# cpu.net
KiCad netlist of a schematic drawn in Altium Designer
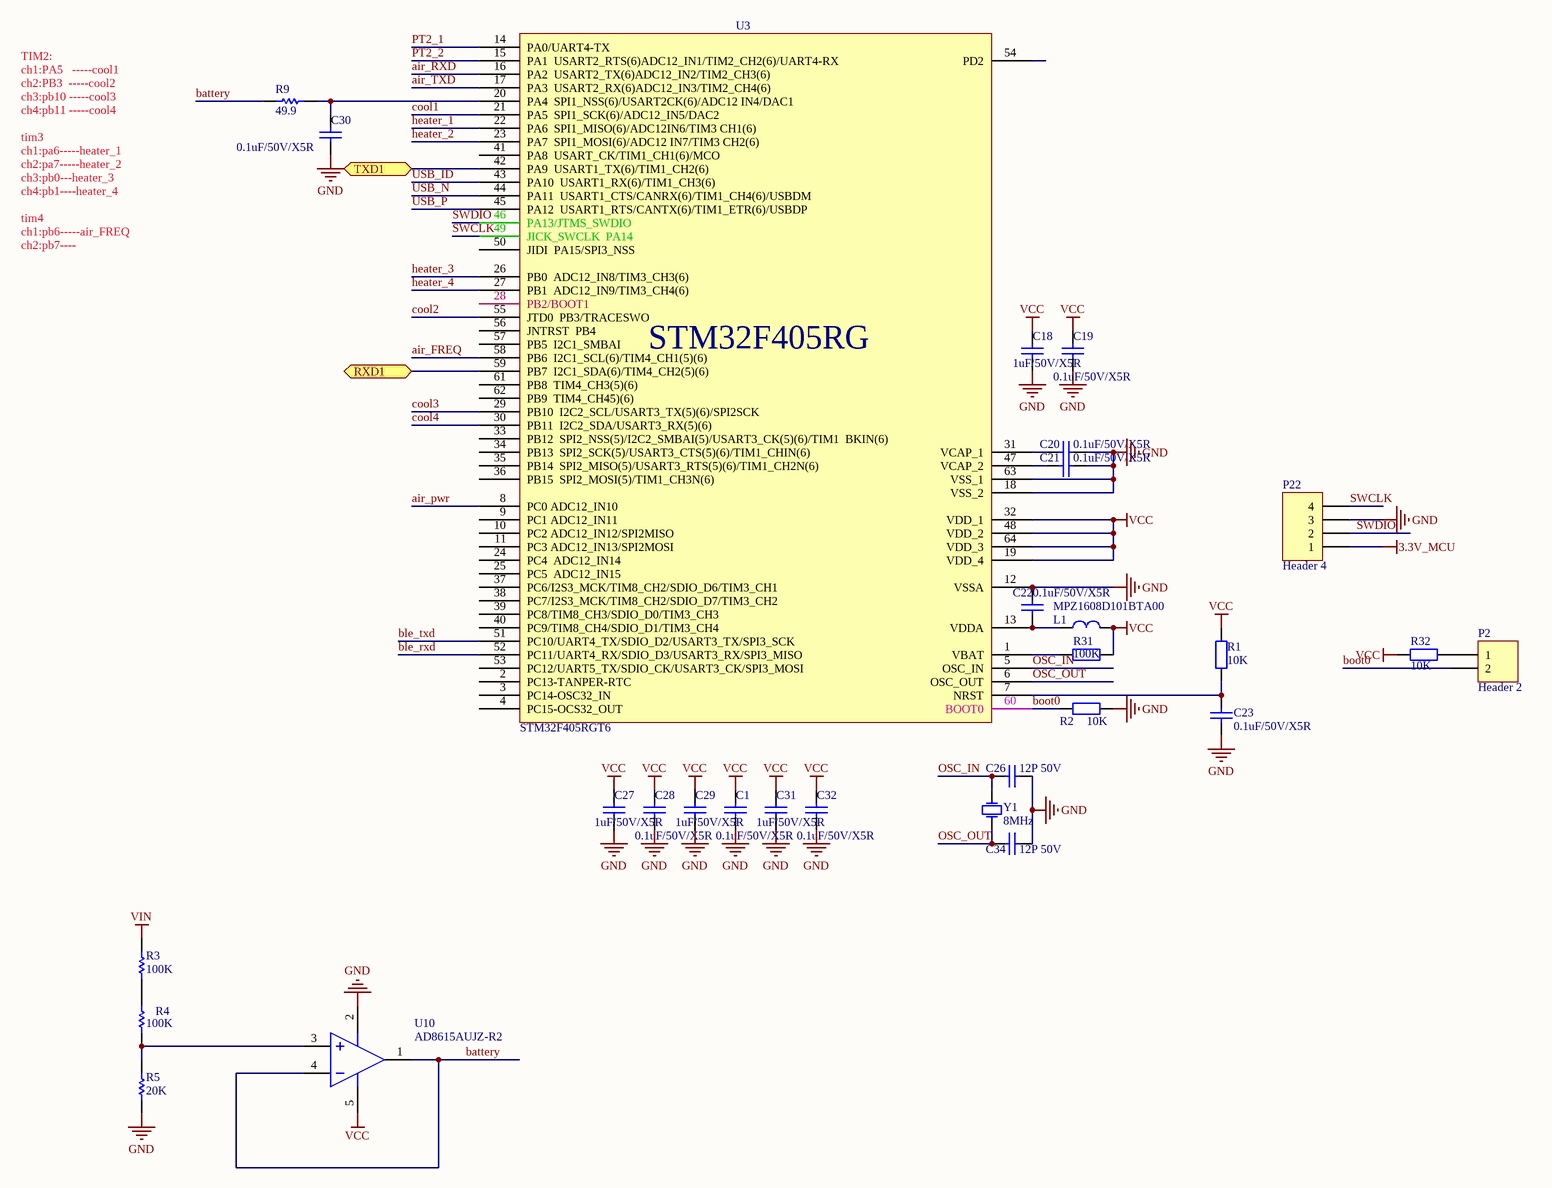
[diagram p0: cpu.SchDoc]

(export (version "E")
  (design (tool "Eeschema 10.0.6"))
  (components
    (comp (ref "C1")
      (value "0.1uF/50V/X5R")
      (footprint "0603C")
      (description "贴片电容 20%")
      (libsource (lib "XiaoyI") (part "CAP4"))
    )
    (comp (ref "C18")
      (value "1uF/50V/X5R")
      (footprint "0603C")
      (description "贴片电容 20%")
      (libsource (lib "XiaoyI") (part "CAP4"))
    )
    (comp (ref "C19")
      (value "0.1uF/50V/X5R")
      (footprint "0603C")
      (description "贴片电容 20%")
      (libsource (lib "XiaoyI") (part "CAP4"))
    )
    (comp (ref "C20")
      (value "0.1uF/50V/X5R")
      (footprint "0603C")
      (description "贴片电容 20%")
      (libsource (lib "XiaoyI") (part "CAP4"))
    )
    (comp (ref "C21")
      (value "0.1uF/50V/X5R")
      (footprint "0603C")
      (description "贴片电容 20%")
      (libsource (lib "XiaoyI") (part "CAP4"))
    )
    (comp (ref "C22")
      (value "0.1uF/50V/X5R")
      (footprint "0603C")
      (description "贴片电容 20%")
      (libsource (lib "XiaoyI") (part "CAP4"))
    )
    (comp (ref "C23")
      (value "0.1uF/50V/X5R")
      (footprint "0603C")
      (description "贴片电容 20%")
      (libsource (lib "XiaoyI") (part "CAP4"))
    )
    (comp (ref "C26")
      (value "12P 50V")
      (footprint "0603C")
      (description "贴片电容 20%")
      (libsource (lib "XiaoyI") (part "CAP4"))
    )
    (comp (ref "C27")
      (value "1uF/50V/X5R")
      (footprint "0603C")
      (description "贴片电容 20%")
      (libsource (lib "XiaoyI") (part "CAP4"))
    )
    (comp (ref "C28")
      (value "0.1uF/50V/X5R")
      (footprint "0603C")
      (description "贴片电容 20%")
      (libsource (lib "XiaoyI") (part "CAP4"))
    )
    (comp (ref "C29")
      (value "1uF/50V/X5R")
      (footprint "0603C")
      (description "贴片电容 20%")
      (libsource (lib "XiaoyI") (part "CAP4"))
    )
    (comp (ref "C30")
      (value "0.1uF/50V/X5R")
      (footprint "0603C")
      (description "贴片电容 20%")
      (libsource (lib "XiaoyI") (part "CAP4"))
    )
    (comp (ref "C31")
      (value "1uF/50V/X5R")
      (footprint "0603C")
      (description "贴片电容 20%")
      (libsource (lib "XiaoyI") (part "CAP4"))
    )
    (comp (ref "C32")
      (value "0.1uF/50V/X5R")
      (footprint "0603C")
      (description "贴片电容 20%")
      (libsource (lib "XiaoyI") (part "CAP4"))
    )
    (comp (ref "C34")
      (value "12P 50V")
      (footprint "0603C")
      (description "贴片电容 20%")
      (libsource (lib "XiaoyI") (part "CAP4"))
    )
    (comp (ref "L1")
      (value "MPZ1608D101BTA00")
      (footprint "0603R")
      (description "磁珠电感 100R 100MHz")
      (libsource (lib "XiaoyI") (part "CIZHU1"))
    )
    (comp (ref "P2")
      (value "Header 2")
      (footprint "HDR1X2")
      (description "Header, 2-Pin")
      (fields (field (name "PUBLISHER") "Altium Limited"))
      (libsource (lib "Miscellaneous Connectors") (part "Header 2"))
    )
    (comp (ref "P22")
      (value "Header 4")
      (footprint "HDR1X4")
      (description "Header, 4-Pin")
      (fields (field (name "PUBLISHER") "Altium Limited"))
      (libsource (lib "Miscellaneous Connectors") (part "Header 4"))
    )
    (comp (ref "R1")
      (value "10K")
      (footprint "0603R")
      (description "贴片电阻 5%")
      (libsource (lib "") (part "RES2_1"))
    )
    (comp (ref "R2")
      (value "10K")
      (footprint "0603R")
      (description "贴片电阻 5%")
      (libsource (lib "XiaoyI") (part "RES2"))
    )
    (comp (ref "R3")
      (value "100K")
      (footprint "0603R")
      (description "Resistor")
      (fields (field (name "PUBLISHER") "Altium Limited"))
      (libsource (lib "Miscellaneous Devices") (part "Res1"))
    )
    (comp (ref "R4")
      (value "100K")
      (footprint "0603R")
      (description "Resistor")
      (fields (field (name "PUBLISHER") "Altium Limited"))
      (libsource (lib "Miscellaneous Devices") (part "Res1"))
    )
    (comp (ref "R5")
      (value "20K")
      (footprint "0603R")
      (description "Resistor")
      (fields (field (name "PUBLISHER") "Altium Limited"))
      (libsource (lib "Miscellaneous Devices") (part "Res1"))
    )
    (comp (ref "R9")
      (value "49.9")
      (footprint "0603R")
      (description "Resistor")
      (fields (field (name "PUBLISHER") "Altium Limited"))
      (libsource (lib "Miscellaneous Devices") (part "Res1"))
    )
    (comp (ref "R31")
      (value "100K")
      (footprint "0603R")
      (description "贴片电阻 5%")
      (libsource (lib "") (part "RES2_2"))
    )
    (comp (ref "R32")
      (value "10K")
      (footprint "0603R")
      (description "贴片电阻 5%")
      (libsource (lib "") (part "RES2_2"))
    )
    (comp (ref "U3")
      (value "STM32F405RGT6")
      (footprint "LQFP-64")
      (description "MCU")
      (libsource (lib "XiaoyI") (part "STM32F405RG"))
    )
    (comp (ref "U10")
      (value "AD8615AUJZ-R2")
      (footprint "sot-23-5")
      (libsource (lib "Schlib1") (part "AD8615"))
    )
    (comp (ref "Y1")
      (value "8MHz")
      (footprint "CRAY_5032")
      (description "晶振")
      (libsource (lib "XiaoyI") (part "XTAL"))
    )
  )
  (nets
    (net (code "1") (name "/OSC_IN") (class "Default")
      (node (ref "C26") (pin "2") (pinfunction "2_2") (pintype "passive"))
      (node (ref "U3") (pin "5") (pinfunction "OSC_IN_5") (pintype "passive"))
      (node (ref "Y1") (pin "2") (pinfunction "OSC2_2") (pintype "passive"))
    )
    (net (code "2") (name "/OSC_OUT") (class "Default")
      (node (ref "C34") (pin "2") (pinfunction "2_2") (pintype "passive"))
      (node (ref "U3") (pin "6") (pinfunction "OSC_OUT_6") (pintype "passive"))
      (node (ref "Y1") (pin "1") (pinfunction "OSC1_1") (pintype "passive"))
    )
    (net (code "3") (name "/PT2_1") (class "Default")
      (node (ref "U3") (pin "14") (pinfunction "PA0/UART4-TX_14") (pintype "passive"))
    )
    (net (code "4") (name "/PT2_2") (class "Default")
      (node (ref "U3") (pin "15") (pinfunction "PA1__USART2_RTS(6)ADC12_IN1/TIM2_CH2(6)/UART4-RX_15") (pintype "passive"))
    )
    (net (code "5") (name "/RXD1") (class "Default")
      (node (ref "U3") (pin "59") (pinfunction "PB7__I2C1_SDA(6)/TIM4_CH2(5)(6)_59") (pintype "passive"))
    )
    (net (code "6") (name "/SWCLK") (class "Default")
      (node (ref "P22") (pin "4") (pinfunction "4_4") (pintype "passive"))
      (node (ref "U3") (pin "49") (pinfunction "JICK_SWCLK__PA14_49") (pintype "passive"))
    )
    (net (code "7") (name "/SWDIO") (class "Default")
      (node (ref "P22") (pin "2") (pinfunction "2_2") (pintype "passive"))
      (node (ref "U3") (pin "46") (pinfunction "PA13/JTMS_SWDIO_46") (pintype "passive"))
    )
    (net (code "8") (name "/TXD1") (class "Default")
      (node (ref "U3") (pin "42") (pinfunction "PA9__USART1_TX(6)/TIM1_CH2(6)_42") (pintype "passive"))
    )
    (net (code "9") (name "/USB_ID") (class "Default")
      (node (ref "U3") (pin "43") (pinfunction "PA10__USART1_RX(6)/TIM1_CH3(6)_43") (pintype "passive"))
    )
    (net (code "10") (name "/USB_N") (class "Default")
      (node (ref "U3") (pin "44") (pinfunction "PA11__USART1_CTS/CANRX(6)/TIM1_CH4(6)/USBDM_44") (pintype "passive"))
    )
    (net (code "11") (name "/USB_P") (class "Default")
      (node (ref "U3") (pin "45") (pinfunction "PA12__USART1_RTS/CANTX(6)/TIM1_ETR(6)/USBDP_45") (pintype "passive"))
    )
    (net (code "12") (name "/air_FREQ") (class "Default")
      (node (ref "U3") (pin "58") (pinfunction "PB6__I2C1_SCL(6)/TIM4_CH1(5)(6)_58") (pintype "passive"))
    )
    (net (code "13") (name "/air_RXD") (class "Default")
      (node (ref "U3") (pin "16") (pinfunction "PA2__USART2_TX(6)ADC12_IN2/TIM2_CH3(6)_16") (pintype "passive"))
    )
    (net (code "14") (name "/air_TXD") (class "Default")
      (node (ref "U3") (pin "17") (pinfunction "PA3__USART2_RX(6)ADC12_IN3/TIM2_CH4(6)_17") (pintype "passive"))
    )
    (net (code "15") (name "/air_pwr") (class "Default")
      (node (ref "U3") (pin "8") (pinfunction "PC0_ADC12_IN10_8") (pintype "passive"))
    )
    (net (code "16") (name "/battery") (class "Default")
      (node (ref "R9") (pin "1") (pinfunction "1_1") (pintype "passive"))
      (node (ref "U10") (pin "1") (pinfunction "OS_NUL_1") (pintype "passive"))
      (node (ref "U10") (pin "4") (pinfunction "V-_4") (pintype "power_in"))
    )
    (net (code "17") (name "/ble_rxd") (class "Default")
      (node (ref "U3") (pin "52") (pinfunction "PC11/UART4_RX/SDIO_D3/USART3_RX/SPI3_MISO_52") (pintype "passive"))
    )
    (net (code "18") (name "/ble_txd") (class "Default")
      (node (ref "U3") (pin "51") (pinfunction "PC10/UART4_TX/SDIO_D2/USART3_TX/SPI3_SCK_51") (pintype "passive"))
    )
    (net (code "19") (name "/boot0") (class "Default")
      (node (ref "P2") (pin "2") (pinfunction "2_2") (pintype "passive"))
      (node (ref "R2") (pin "1") (pinfunction "1_1") (pintype "passive"))
      (node (ref "U3") (pin "60") (pinfunction "BOOT0_60") (pintype "passive"))
    )
    (net (code "20") (name "/cool1") (class "Default")
      (node (ref "U3") (pin "21") (pinfunction "PA5__SPI1_SCK(6)/ADC12_IN5/DAC2_21") (pintype "passive"))
    )
    (net (code "21") (name "/cool2") (class "Default")
      (node (ref "U3") (pin "55") (pinfunction "JTD0__PB3/TRACESWO_55") (pintype "passive"))
    )
    (net (code "22") (name "/cool3") (class "Default")
      (node (ref "U3") (pin "29") (pinfunction "PB10__I2C2_SCL/USART3_TX(5)(6)/SPI2SCK_29") (pintype "passive"))
    )
    (net (code "23") (name "/cool4") (class "Default")
      (node (ref "U3") (pin "30") (pinfunction "PB11__I2C2_SDA/USART3_RX(5)(6)_30") (pintype "passive"))
    )
    (net (code "24") (name "/heater_1") (class "Default")
      (node (ref "U3") (pin "22") (pinfunction "PA6__SPI1_MISO(6)/ADC12IN6/TIM3_CH1(6)_22") (pintype "passive"))
    )
    (net (code "25") (name "/heater_2") (class "Default")
      (node (ref "U3") (pin "23") (pinfunction "PA7__SPI1_MOSI(6)/ADC12_IN7/TIM3_CH2(6)_23") (pintype "passive"))
    )
    (net (code "26") (name "/heater_3") (class "Default")
      (node (ref "U3") (pin "26") (pinfunction "PB0__ADC12_IN8/TIM3_CH3(6)_26") (pintype "passive"))
    )
    (net (code "27") (name "/heater_4") (class "Default")
      (node (ref "U3") (pin "27") (pinfunction "PB1__ADC12_IN9/TIM3_CH4(6)_27") (pintype "passive"))
    )
    (net (code "28") (name "3.3V_MCU") (class "Default")
      (node (ref "P22") (pin "1") (pinfunction "1_1") (pintype "passive"))
    )
    (net (code "29") (name "GND") (class "Default")
      (node (ref "C1") (pin "1") (pinfunction "1_1") (pintype "passive"))
      (node (ref "C18") (pin "1") (pinfunction "1_1") (pintype "passive"))
      (node (ref "C19") (pin "1") (pinfunction "1_1") (pintype "passive"))
      (node (ref "C20") (pin "1") (pinfunction "1_1") (pintype "passive"))
      (node (ref "C21") (pin "1") (pinfunction "1_1") (pintype "passive"))
      (node (ref "C22") (pin "1") (pinfunction "1_1") (pintype "passive"))
      (node (ref "C23") (pin "1") (pinfunction "1_1") (pintype "passive"))
      (node (ref "C26") (pin "1") (pinfunction "1_1") (pintype "passive"))
      (node (ref "C27") (pin "1") (pinfunction "1_1") (pintype "passive"))
      (node (ref "C28") (pin "1") (pinfunction "1_1") (pintype "passive"))
      (node (ref "C29") (pin "1") (pinfunction "1_1") (pintype "passive"))
      (node (ref "C30") (pin "1") (pinfunction "1_1") (pintype "passive"))
      (node (ref "C31") (pin "1") (pinfunction "1_1") (pintype "passive"))
      (node (ref "C32") (pin "1") (pinfunction "1_1") (pintype "passive"))
      (node (ref "C34") (pin "1") (pinfunction "1_1") (pintype "passive"))
      (node (ref "P22") (pin "3") (pinfunction "3_3") (pintype "passive"))
      (node (ref "R2") (pin "2") (pinfunction "2_2") (pintype "passive"))
      (node (ref "R5") (pin "2") (pinfunction "2_2") (pintype "passive"))
      (node (ref "U10") (pin "2") (pinfunction "G_2") (pintype "power_in"))
      (node (ref "U3") (pin "12") (pinfunction "VSSA_12") (pintype "passive"))
      (node (ref "U3") (pin "18") (pinfunction "VSS_2_18") (pintype "passive"))
      (node (ref "U3") (pin "63") (pinfunction "VSS_1_63") (pintype "passive"))
    )
    (net (code "30") (name "Net-(P2-Pad1)") (class "Default")
      (node (ref "P2") (pin "1") (pinfunction "1_1") (pintype "passive"))
      (node (ref "R32") (pin "1") (pinfunction "1_1") (pintype "passive"))
    )
    (net (code "31") (name "Net-(R3-Pad2)") (class "Default")
      (node (ref "R3") (pin "2") (pinfunction "2_2") (pintype "passive"))
      (node (ref "R4") (pin "1") (pinfunction "1_1") (pintype "passive"))
    )
    (net (code "32") (name "Net-(U3-NRST)") (class "Default")
      (node (ref "C23") (pin "2") (pinfunction "2_2") (pintype "passive"))
      (node (ref "R1") (pin "2") (pinfunction "2_2") (pintype "passive"))
      (node (ref "U3") (pin "7") (pinfunction "NRST_7") (pintype "passive"))
    )
    (net (code "33") (name "Net-(U3-PA4__SPI1_NSS(6){slash}USART2CK(6){slash}ADC12_IN4{slash}DAC1)") (class "Default")
      (node (ref "C30") (pin "2") (pinfunction "2_2") (pintype "passive"))
      (node (ref "R9") (pin "2") (pinfunction "2_2") (pintype "passive"))
      (node (ref "U3") (pin "20") (pinfunction "PA4__SPI1_NSS(6)/USART2CK(6)/ADC12_IN4/DAC1_20") (pintype "passive"))
    )
    (net (code "34") (name "Net-(U3-VBAT)") (class "Default")
      (node (ref "R31") (pin "2") (pinfunction "2_2") (pintype "passive"))
      (node (ref "U3") (pin "1") (pinfunction "VBAT_1") (pintype "passive"))
    )
    (net (code "35") (name "Net-(U3-VCAP_1)") (class "Default")
      (node (ref "C20") (pin "2") (pinfunction "2_2") (pintype "passive"))
      (node (ref "U3") (pin "31") (pinfunction "VCAP_1_31") (pintype "passive"))
    )
    (net (code "36") (name "Net-(U3-VCAP_2)") (class "Default")
      (node (ref "C21") (pin "2") (pinfunction "2_2") (pintype "passive"))
      (node (ref "U3") (pin "47") (pinfunction "VCAP_2_47") (pintype "passive"))
    )
    (net (code "37") (name "Net-(U3-VDDA)") (class "Default")
      (node (ref "C22") (pin "2") (pinfunction "2_2") (pintype "passive"))
      (node (ref "L1") (pin "1") (pinfunction "1_1") (pintype "passive"))
      (node (ref "U3") (pin "13") (pinfunction "VDDA_13") (pintype "passive"))
    )
    (net (code "38") (name "Net-(U10-V+)") (class "Default")
      (node (ref "R4") (pin "2") (pinfunction "2_2") (pintype "passive"))
      (node (ref "R5") (pin "1") (pinfunction "1_1") (pintype "passive"))
      (node (ref "U10") (pin "3") (pinfunction "V+_3") (pintype "power_in"))
    )
    (net (code "39") (name "VCC") (class "Default")
      (node (ref "C1") (pin "2") (pinfunction "2_2") (pintype "passive"))
      (node (ref "C18") (pin "2") (pinfunction "2_2") (pintype "passive"))
      (node (ref "C19") (pin "2") (pinfunction "2_2") (pintype "passive"))
      (node (ref "C27") (pin "2") (pinfunction "2_2") (pintype "passive"))
      (node (ref "C28") (pin "2") (pinfunction "2_2") (pintype "passive"))
      (node (ref "C29") (pin "2") (pinfunction "2_2") (pintype "passive"))
      (node (ref "C31") (pin "2") (pinfunction "2_2") (pintype "passive"))
      (node (ref "C32") (pin "2") (pinfunction "2_2") (pintype "passive"))
      (node (ref "L1") (pin "2") (pinfunction "2_2") (pintype "passive"))
      (node (ref "R1") (pin "1") (pinfunction "1_1") (pintype "passive"))
      (node (ref "R31") (pin "1") (pinfunction "1_1") (pintype "passive"))
      (node (ref "R32") (pin "2") (pinfunction "2_2") (pintype "passive"))
      (node (ref "U10") (pin "5") (pinfunction "VCC_5") (pintype "passive"))
      (node (ref "U3") (pin "19") (pinfunction "VDD_4_19") (pintype "passive"))
      (node (ref "U3") (pin "32") (pinfunction "VDD_1_32") (pintype "passive"))
      (node (ref "U3") (pin "48") (pinfunction "VDD_2_48") (pintype "passive"))
      (node (ref "U3") (pin "64") (pinfunction "VDD_3_64") (pintype "passive"))
    )
    (net (code "40") (name "VIN") (class "Default")
      (node (ref "R3") (pin "1") (pinfunction "1_1") (pintype "passive"))
    )
    (net (code "41") (name "unconnected-(U3-JIDI__PA15{slash}SPI3_NSS-Pad50)") (class "Default")
      (node (ref "U3") (pin "50") (pinfunction "JIDI__PA15/SPI3_NSS_50") (pintype "passive"))
    )
    (net (code "42") (name "unconnected-(U3-JNTRST__PB4-Pad56)") (class "Default")
      (node (ref "U3") (pin "56") (pinfunction "JNTRST__PB4_56") (pintype "passive"))
    )
    (net (code "43") (name "unconnected-(U3-PA8__USART_CK{slash}TIM1_CH1(6){slash}MCO-Pad41)") (class "Default")
      (node (ref "U3") (pin "41") (pinfunction "PA8__USART_CK/TIM1_CH1(6)/MCO_41") (pintype "passive"))
    )
    (net (code "44") (name "unconnected-(U3-PB2{slash}BOOT1-Pad28)") (class "Default")
      (node (ref "U3") (pin "28") (pinfunction "PB2/BOOT1_28") (pintype "passive"))
    )
    (net (code "45") (name "unconnected-(U3-PB5__I2C1_SMBAI-Pad57)") (class "Default")
      (node (ref "U3") (pin "57") (pinfunction "PB5__I2C1_SMBAI_57") (pintype "passive"))
    )
    (net (code "46") (name "unconnected-(U3-PB8__TIM4_CH3(5)(6)-Pad61)") (class "Default")
      (node (ref "U3") (pin "61") (pinfunction "PB8__TIM4_CH3(5)(6)_61") (pintype "passive"))
    )
    (net (code "47") (name "unconnected-(U3-PB9__TIM4_CH45)(6)-Pad62)") (class "Default")
      (node (ref "U3") (pin "62") (pinfunction "PB9__TIM4_CH45)(6)_62") (pintype "passive"))
    )
    (net (code "48") (name "unconnected-(U3-PB12__SPI2_NSS(5){slash}I2C2_SMBAI(5){slash}USART3_CK(5)(6){slash}TIM1__BKIN(6)-Pad33)") (class "Default")
      (node (ref "U3") (pin "33") (pinfunction "PB12__SPI2_NSS(5)/I2C2_SMBAI(5)/USART3_CK(5)(6)/TIM1__BKIN(6)_33") (pintype "passive"))
    )
    (net (code "49") (name "unconnected-(U3-PB13__SPI2_SCK(5){slash}USART3_CTS(5)(6){slash}TIM1_CHIN(6)-Pad34)") (class "Default")
      (node (ref "U3") (pin "34") (pinfunction "PB13__SPI2_SCK(5)/USART3_CTS(5)(6)/TIM1_CHIN(6)_34") (pintype "passive"))
    )
    (net (code "50") (name "unconnected-(U3-PB14__SPI2_MISO(5){slash}USART3_RTS(5)(6){slash}TIM1_CH2N(6)-Pad35)") (class "Default")
      (node (ref "U3") (pin "35") (pinfunction "PB14__SPI2_MISO(5)/USART3_RTS(5)(6)/TIM1_CH2N(6)_35") (pintype "passive"))
    )
    (net (code "51") (name "unconnected-(U3-PB15__SPI2_MOSI(5){slash}TIM1_CH3N(6)-Pad36)") (class "Default")
      (node (ref "U3") (pin "36") (pinfunction "PB15__SPI2_MOSI(5)/TIM1_CH3N(6)_36") (pintype "passive"))
    )
    (net (code "52") (name "unconnected-(U3-PC1_ADC12_IN11-Pad9)") (class "Default")
      (node (ref "U3") (pin "9") (pinfunction "PC1_ADC12_IN11_9") (pintype "passive"))
    )
    (net (code "53") (name "unconnected-(U3-PC2_ADC12_IN12{slash}SPI2MISO-Pad10)") (class "Default")
      (node (ref "U3") (pin "10") (pinfunction "PC2_ADC12_IN12/SPI2MISO_10") (pintype "passive"))
    )
    (net (code "54") (name "unconnected-(U3-PC3_ADC12_IN13{slash}SPI2MOSI-Pad11)") (class "Default")
      (node (ref "U3") (pin "11") (pinfunction "PC3_ADC12_IN13/SPI2MOSI_11") (pintype "passive"))
    )
    (net (code "55") (name "unconnected-(U3-PC4__ADC12_IN14-Pad24)") (class "Default")
      (node (ref "U3") (pin "24") (pinfunction "PC4__ADC12_IN14_24") (pintype "passive"))
    )
    (net (code "56") (name "unconnected-(U3-PC5__ADC12_IN15-Pad25)") (class "Default")
      (node (ref "U3") (pin "25") (pinfunction "PC5__ADC12_IN15_25") (pintype "passive"))
    )
    (net (code "57") (name "unconnected-(U3-PC6{slash}I2S3_MCK{slash}TIM8_CH2{slash}SDIO_D6{slash}TIM3_CH1-Pad37)") (class "Default")
      (node (ref "U3") (pin "37") (pinfunction "PC6/I2S3_MCK/TIM8_CH2/SDIO_D6/TIM3_CH1_37") (pintype "passive"))
    )
    (net (code "58") (name "unconnected-(U3-PC7{slash}I2S3_MCK{slash}TIM8_CH2{slash}SDIO_D7{slash}TIM3_CH2-Pad38)") (class "Default")
      (node (ref "U3") (pin "38") (pinfunction "PC7/I2S3_MCK/TIM8_CH2/SDIO_D7/TIM3_CH2_38") (pintype "passive"))
    )
    (net (code "59") (name "unconnected-(U3-PC8{slash}TIM8_CH3{slash}SDIO_D0{slash}TIM3_CH3-Pad39)") (class "Default")
      (node (ref "U3") (pin "39") (pinfunction "PC8/TIM8_CH3/SDIO_D0/TIM3_CH3_39") (pintype "passive"))
    )
    (net (code "60") (name "unconnected-(U3-PC9{slash}TIM8_CH4{slash}SDIO_D1{slash}TIM3_CH4-Pad40)") (class "Default")
      (node (ref "U3") (pin "40") (pinfunction "PC9/TIM8_CH4/SDIO_D1/TIM3_CH4_40") (pintype "passive"))
    )
    (net (code "61") (name "unconnected-(U3-PC12{slash}UART5_TX{slash}SDIO_CK{slash}USART3_CK{slash}SPI3_MOSI-Pad53)") (class "Default")
      (node (ref "U3") (pin "53") (pinfunction "PC12/UART5_TX/SDIO_CK/USART3_CK/SPI3_MOSI_53") (pintype "passive"))
    )
    (net (code "62") (name "unconnected-(U3-PC13-TANPER-RTC-Pad2)") (class "Default")
      (node (ref "U3") (pin "2") (pinfunction "PC13-TANPER-RTC_2") (pintype "passive"))
    )
    (net (code "63") (name "unconnected-(U3-PC14-OSC32_IN-Pad3)") (class "Default")
      (node (ref "U3") (pin "3") (pinfunction "PC14-OSC32_IN_3") (pintype "passive"))
    )
    (net (code "64") (name "unconnected-(U3-PC15-OCS32_OUT-Pad4)") (class "Default")
      (node (ref "U3") (pin "4") (pinfunction "PC15-OCS32_OUT_4") (pintype "passive"))
    )
    (net (code "65") (name "unconnected-(U3-PD2-Pad54)") (class "Default")
      (node (ref "U3") (pin "54") (pinfunction "PD2_54") (pintype "passive"))
    )
  )
)
